# 4046.net
KiCad netlist of a schematic drawn in EasyEDA Pro
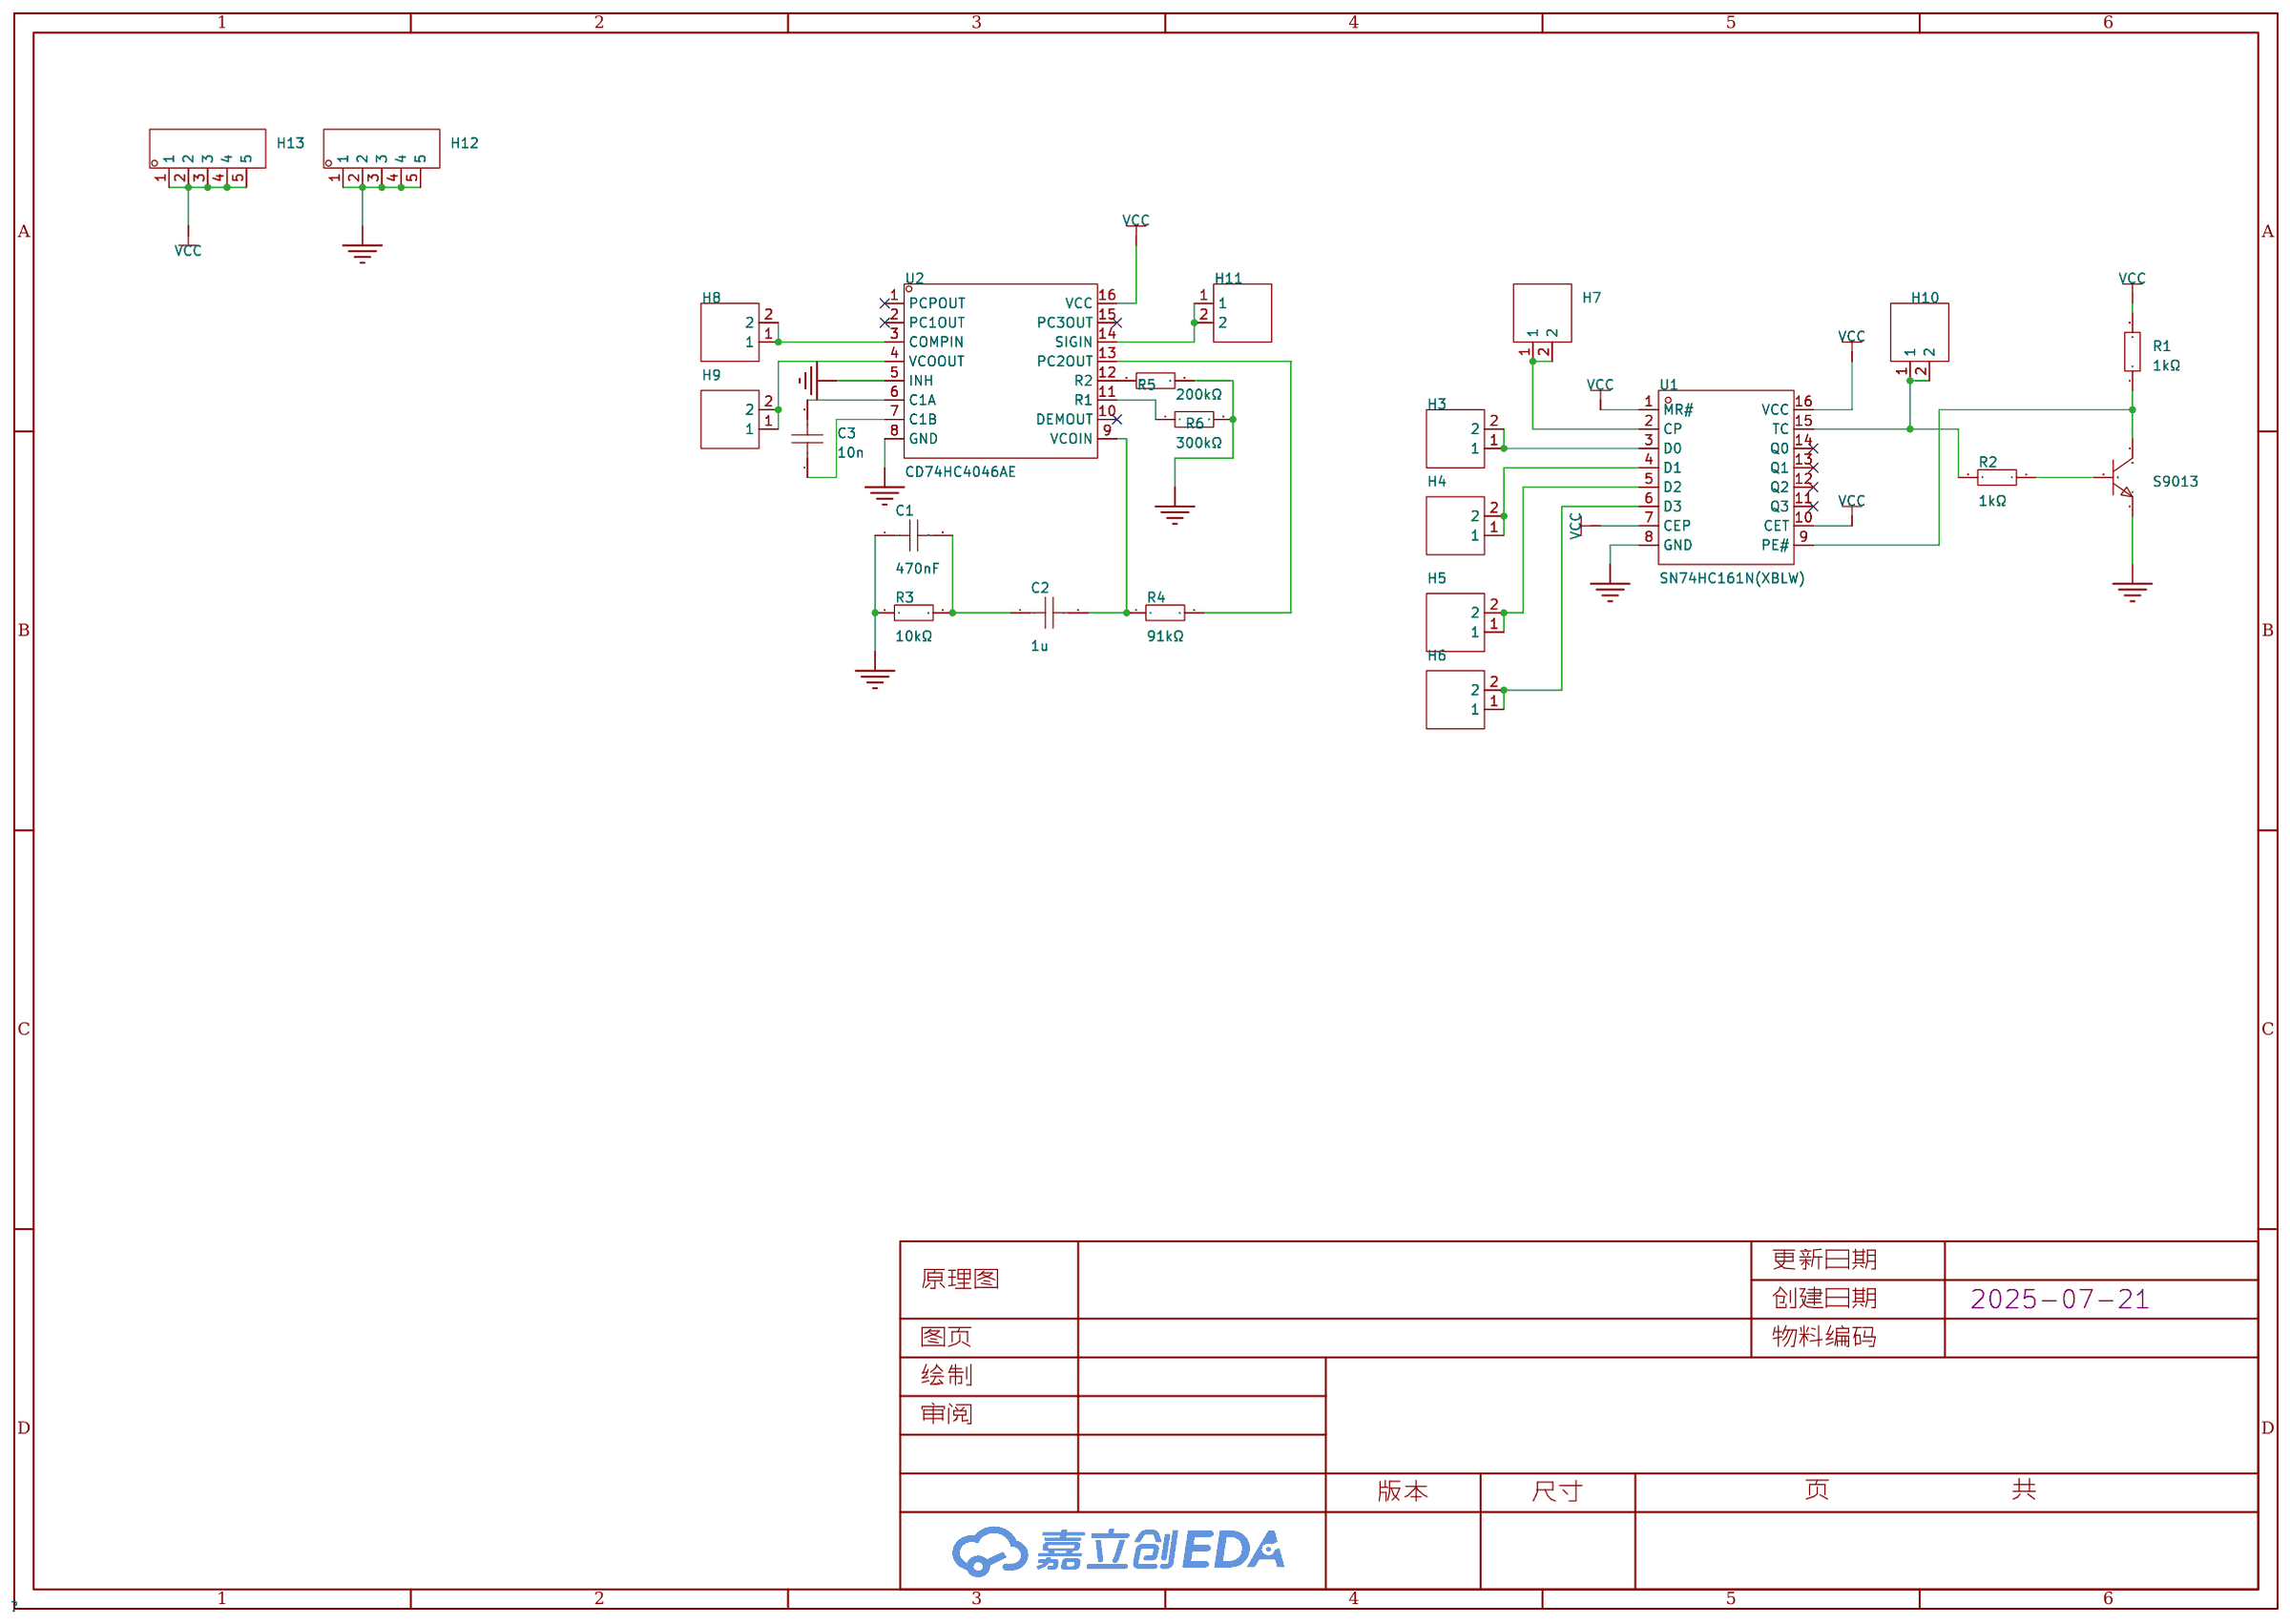
[diagram p0: schematic sheet]

(export (version "E")
  (design (tool "Eeschema 10.0.6"))
  (components
    (comp (ref "C1")
      (value "470nF")
      (footprint "easyedapro:CAP-TH_L8.5-W5.0-P5.00-D1.2")
      (description "容值:100nF;精度:±10%;额定电压:50V;温度系数:X7R;")
      (fields (field (name "Manufacturer Part") "CT4-0805B104K500F3") (field (name "Manufacturer") "FH(风华)"))
      (libsource (lib "easyedapro") (part "CT4-0805B104K500F3"))
    )
    (comp (ref "C2")
      (value "1u")
      (footprint "easyedapro:CAP-TH_L8.5-W5.0-P5.00-D1.2")
      (description "容值:100nF;精度:±10%;额定电压:50V;温度系数:X7R;")
      (fields (field (name "Manufacturer Part") "CT4-0805B104K500F3") (field (name "Manufacturer") "FH(风华)"))
      (libsource (lib "easyedapro") (part "CT4-0805B104K500F3"))
    )
    (comp (ref "C3")
      (value "10n")
      (footprint "easyedapro:CAP-TH_L8.5-W5.0-P5.00-D1.2")
      (description "容值:100nF;精度:±10%;额定电压:50V;温度系数:X7R;")
      (fields (field (name "Manufacturer Part") "CT4-0805B104K500F3") (field (name "Manufacturer") "FH(风华)"))
      (libsource (lib "easyedapro") (part "CT4-0805B104K500F3"))
    )
    (comp (ref "H3")
      (value "~")
      (footprint "easyedapro:HDR-TH_2P-P2.54-V-M-1")
      (libsource (lib "easyedapro") (part "210S-1*2P L=11.6MMGold-plated black"))
    )
    (comp (ref "H4")
      (value "~")
      (footprint "easyedapro:HDR-TH_2P-P2.54-V-M-1")
      (libsource (lib "easyedapro") (part "210S-1*2P L=11.6MMGold-plated black"))
    )
    (comp (ref "H5")
      (value "~")
      (footprint "easyedapro:HDR-TH_2P-P2.54-V-M-1")
      (libsource (lib "easyedapro") (part "210S-1*2P L=11.6MMGold-plated black"))
    )
    (comp (ref "H6")
      (value "~")
      (footprint "easyedapro:HDR-TH_2P-P2.54-V-M-1")
      (libsource (lib "easyedapro") (part "210S-1*2P L=11.6MMGold-plated black"))
    )
    (comp (ref "H7")
      (value "~")
      (footprint "easyedapro:HDR-TH_2P-P2.54-V-M-1")
      (libsource (lib "easyedapro") (part "210S-1*2P L=11.6MMGold-plated black"))
    )
    (comp (ref "H8")
      (value "~")
      (footprint "easyedapro:HDR-TH_2P-P2.54-V-M-1")
      (libsource (lib "easyedapro") (part "210S-1*2P L=11.6MMGold-plated black"))
    )
    (comp (ref "H9")
      (value "~")
      (footprint "easyedapro:HDR-TH_2P-P2.54-V-M-1")
      (libsource (lib "easyedapro") (part "210S-1*2P L=11.6MMGold-plated black"))
    )
    (comp (ref "H10")
      (value "~")
      (footprint "easyedapro:HDR-TH_2P-P2.54-V-M-1")
      (libsource (lib "easyedapro") (part "210S-1*2P L=11.6MMGold-plated black"))
    )
    (comp (ref "H11")
      (value "~")
      (footprint "easyedapro:HDR-TH_2P-P2.54-V-M-1")
      (libsource (lib "easyedapro") (part "210S-1*2P L=11.6MMGold-plated black"))
    )
    (comp (ref "H12")
      (value "~")
      (footprint "easyedapro:HDR-TH_5P-P2.54-V-M")
      (libsource (lib "easyedapro") (part "MTP125-1105S1"))
    )
    (comp (ref "H13")
      (value "~")
      (footprint "easyedapro:HDR-TH_5P-P2.54-V-M")
      (libsource (lib "easyedapro") (part "MTP125-1105S1"))
    )
    (comp (ref "Q1")
      (value "S9013")
      (footprint "easyedapro:TO-92-3_L4.5-W3.5-P1.27-L")
      (description "晶体管类型:NPN;集电极电流(Ic):500mA;直流电流增益(hFE):300;")
      (fields (field (name "Manufacturer") "HXY MOSFET(华轩阳电子)"))
      (libsource (lib "easyedapro") (part "S9013_C20616377"))
    )
    (comp (ref "R1")
      (value "1kΩ")
      (footprint "easyedapro:Res_1/8W")
      (libsource (lib "easyedapro") (part "电阻"))
    )
    (comp (ref "R2")
      (value "1kΩ")
      (footprint "easyedapro:Res_1/8W")
      (libsource (lib "easyedapro") (part "电阻"))
    )
    (comp (ref "R3")
      (value "10kΩ")
      (footprint "easyedapro:Res_1/8W")
      (libsource (lib "easyedapro") (part "电阻"))
    )
    (comp (ref "R4")
      (value "91kΩ")
      (footprint "easyedapro:Res_1/8W")
      (libsource (lib "easyedapro") (part "电阻"))
    )
    (comp (ref "R5")
      (value "200kΩ")
      (footprint "easyedapro:Res_1/8W")
      (libsource (lib "easyedapro") (part "电阻"))
    )
    (comp (ref "R6")
      (value "300kΩ")
      (footprint "easyedapro:Res_1/8W")
      (libsource (lib "easyedapro") (part "电阻"))
    )
    (comp (ref "U1")
      (value "SN74HC161N(XBLW)")
      (footprint "easyedapro:PDIP-16_L19.3-W6.4-P2.54-LS7.9-BL")
      (description "工作电压:2V~6V;触发沿:上升沿;计数速率:48MHz;")
      (fields (field (name "Manufacturer") "XBLW(芯伯乐)"))
      (libsource (lib "easyedapro") (part "SN74HC161N(XBLW)"))
    )
    (comp (ref "U2")
      (value "CD74HC4046AE")
      (footprint "easyedapro:PDIP-16_L22.1-W6.3-P2.54-LS7.6-BL")
      (description "最大输出频率:38MHz;输出通道数:3;")
      (fields (field (name "Manufacturer") "TI(德州仪器)"))
      (libsource (lib "easyedapro") (part "CD74HC4046AE"))
    )
  )
  (nets
    (net (code "1") (name "GND") (class "Default")
      (node (ref "C1") (pin "1") (pinfunction "1_1") (pintype "unspecified"))
      (node (ref "H12") (pin "1") (pinfunction "1_1") (pintype "unspecified"))
      (node (ref "H12") (pin "2") (pinfunction "2_2") (pintype "unspecified"))
      (node (ref "H12") (pin "3") (pinfunction "3_3") (pintype "unspecified"))
      (node (ref "H12") (pin "4") (pinfunction "4_4") (pintype "unspecified"))
      (node (ref "H12") (pin "5") (pinfunction "5_5") (pintype "unspecified"))
      (node (ref "Q1") (pin "1") (pinfunction "E_1") (pintype "unspecified"))
      (node (ref "R3") (pin "1") (pinfunction "1_1") (pintype "input"))
      (node (ref "R5") (pin "2") (pinfunction "2_2") (pintype "input"))
      (node (ref "R6") (pin "2") (pinfunction "2_2") (pintype "input"))
      (node (ref "U1") (pin "8") (pinfunction "GND_8") (pintype "unspecified"))
      (node (ref "U2") (pin "5") (pinfunction "INH_5") (pintype "unspecified"))
      (node (ref "U2") (pin "8") (pinfunction "GND_8") (pintype "unspecified"))
    )
    (net (code "2") (name "Net-(C1-Pad2)") (class "Default")
      (node (ref "C1") (pin "2") (pinfunction "2_2") (pintype "unspecified"))
      (node (ref "C2") (pin "1") (pinfunction "1_1") (pintype "unspecified"))
      (node (ref "R3") (pin "2") (pinfunction "2_2") (pintype "input"))
    )
    (net (code "3") (name "Net-(Q1-B)") (class "Default")
      (node (ref "Q1") (pin "2") (pinfunction "B_2") (pintype "unspecified"))
      (node (ref "R2") (pin "1") (pinfunction "1_1") (pintype "input"))
    )
    (net (code "4") (name "Net-(Q1-C)") (class "Default")
      (node (ref "Q1") (pin "3") (pinfunction "C_3") (pintype "unspecified"))
      (node (ref "R1") (pin "1") (pinfunction "1_1") (pintype "input"))
      (node (ref "U1") (pin "9") (pinfunction "PE#_9") (pintype "unspecified"))
    )
    (net (code "5") (name "Net-(U1-CP)") (class "Default")
      (node (ref "H7") (pin "1") (pinfunction "1_1") (pintype "unspecified"))
      (node (ref "H7") (pin "2") (pinfunction "2_2") (pintype "unspecified"))
      (node (ref "U1") (pin "2") (pinfunction "CP_2") (pintype "unspecified"))
    )
    (net (code "6") (name "Net-(U1-D0)") (class "Default")
      (node (ref "H3") (pin "1") (pinfunction "1_1") (pintype "unspecified"))
      (node (ref "H3") (pin "2") (pinfunction "2_2") (pintype "unspecified"))
      (node (ref "U1") (pin "3") (pinfunction "D0_3") (pintype "unspecified"))
    )
    (net (code "7") (name "Net-(U1-D1)") (class "Default")
      (node (ref "H4") (pin "1") (pinfunction "1_1") (pintype "unspecified"))
      (node (ref "H4") (pin "2") (pinfunction "2_2") (pintype "unspecified"))
      (node (ref "U1") (pin "4") (pinfunction "D1_4") (pintype "unspecified"))
    )
    (net (code "8") (name "Net-(U1-D2)") (class "Default")
      (node (ref "H5") (pin "1") (pinfunction "1_1") (pintype "unspecified"))
      (node (ref "H5") (pin "2") (pinfunction "2_2") (pintype "unspecified"))
      (node (ref "U1") (pin "5") (pinfunction "D2_5") (pintype "unspecified"))
    )
    (net (code "9") (name "Net-(U1-D3)") (class "Default")
      (node (ref "H6") (pin "1") (pinfunction "1_1") (pintype "unspecified"))
      (node (ref "H6") (pin "2") (pinfunction "2_2") (pintype "unspecified"))
      (node (ref "U1") (pin "6") (pinfunction "D3_6") (pintype "unspecified"))
    )
    (net (code "10") (name "Net-(U1-TC)") (class "Default")
      (node (ref "H10") (pin "1") (pinfunction "1_1") (pintype "unspecified"))
      (node (ref "H10") (pin "2") (pinfunction "2_2") (pintype "unspecified"))
      (node (ref "R2") (pin "2") (pinfunction "2_2") (pintype "input"))
      (node (ref "U1") (pin "15") (pinfunction "TC_15") (pintype "unspecified"))
    )
    (net (code "11") (name "Net-(U2-C1A)") (class "Default")
      (node (ref "C3") (pin "2") (pinfunction "2_2") (pintype "unspecified"))
      (node (ref "U2") (pin "6") (pinfunction "C1A_6") (pintype "unspecified"))
    )
    (net (code "12") (name "Net-(U2-C1B)") (class "Default")
      (node (ref "C3") (pin "1") (pinfunction "1_1") (pintype "unspecified"))
      (node (ref "U2") (pin "7") (pinfunction "C1B_7") (pintype "unspecified"))
    )
    (net (code "13") (name "Net-(U2-COMPIN)") (class "Default")
      (node (ref "H8") (pin "1") (pinfunction "1_1") (pintype "unspecified"))
      (node (ref "H8") (pin "2") (pinfunction "2_2") (pintype "unspecified"))
      (node (ref "U2") (pin "3") (pinfunction "COMPIN_3") (pintype "unspecified"))
    )
    (net (code "14") (name "Net-(U2-PC2OUT)") (class "Default")
      (node (ref "R4") (pin "2") (pinfunction "2_2") (pintype "input"))
      (node (ref "U2") (pin "13") (pinfunction "PC2OUT_13") (pintype "unspecified"))
    )
    (net (code "15") (name "Net-(U2-R1)") (class "Default")
      (node (ref "R6") (pin "1") (pinfunction "1_1") (pintype "input"))
      (node (ref "U2") (pin "11") (pinfunction "R1_11") (pintype "unspecified"))
    )
    (net (code "16") (name "Net-(U2-R2)") (class "Default")
      (node (ref "R5") (pin "1") (pinfunction "1_1") (pintype "input"))
      (node (ref "U2") (pin "12") (pinfunction "R2_12") (pintype "unspecified"))
    )
    (net (code "17") (name "Net-(U2-SIGIN)") (class "Default")
      (node (ref "H11") (pin "1") (pinfunction "1_1") (pintype "unspecified"))
      (node (ref "H11") (pin "2") (pinfunction "2_2") (pintype "unspecified"))
      (node (ref "U2") (pin "14") (pinfunction "SIGIN_14") (pintype "unspecified"))
    )
    (net (code "18") (name "Net-(U2-VCOIN)") (class "Default")
      (node (ref "C2") (pin "2") (pinfunction "2_2") (pintype "unspecified"))
      (node (ref "R4") (pin "1") (pinfunction "1_1") (pintype "input"))
      (node (ref "U2") (pin "9") (pinfunction "VCOIN_9") (pintype "unspecified"))
    )
    (net (code "19") (name "Net-(U2-VCOOUT)") (class "Default")
      (node (ref "H9") (pin "1") (pinfunction "1_1") (pintype "unspecified"))
      (node (ref "H9") (pin "2") (pinfunction "2_2") (pintype "unspecified"))
      (node (ref "U2") (pin "4") (pinfunction "VCOOUT_4") (pintype "unspecified"))
    )
    (net (code "20") (name "VCC") (class "Default")
      (node (ref "H13") (pin "1") (pinfunction "1_1") (pintype "unspecified"))
      (node (ref "H13") (pin "2") (pinfunction "2_2") (pintype "unspecified"))
      (node (ref "H13") (pin "3") (pinfunction "3_3") (pintype "unspecified"))
      (node (ref "H13") (pin "4") (pinfunction "4_4") (pintype "unspecified"))
      (node (ref "H13") (pin "5") (pinfunction "5_5") (pintype "unspecified"))
      (node (ref "R1") (pin "2") (pinfunction "2_2") (pintype "input"))
      (node (ref "U1") (pin "1") (pinfunction "MR#_1") (pintype "unspecified"))
      (node (ref "U1") (pin "10") (pinfunction "CET_10") (pintype "unspecified"))
      (node (ref "U1") (pin "16") (pinfunction "VCC_16") (pintype "unspecified"))
      (node (ref "U1") (pin "7") (pinfunction "CEP_7") (pintype "unspecified"))
      (node (ref "U2") (pin "16") (pinfunction "VCC_16") (pintype "unspecified"))
    )
    (net (code "21") (name "unconnected-(U1-Q0-Pad14)") (class "Default")
      (node (ref "U1") (pin "14") (pinfunction "Q0_14") (pintype "unspecified+no_connect"))
    )
    (net (code "22") (name "unconnected-(U1-Q1-Pad13)") (class "Default")
      (node (ref "U1") (pin "13") (pinfunction "Q1_13") (pintype "unspecified+no_connect"))
    )
    (net (code "23") (name "unconnected-(U1-Q2-Pad12)") (class "Default")
      (node (ref "U1") (pin "12") (pinfunction "Q2_12") (pintype "unspecified+no_connect"))
    )
    (net (code "24") (name "unconnected-(U1-Q3-Pad11)") (class "Default")
      (node (ref "U1") (pin "11") (pinfunction "Q3_11") (pintype "unspecified+no_connect"))
    )
    (net (code "25") (name "unconnected-(U2-DEMOUT-Pad10)") (class "Default")
      (node (ref "U2") (pin "10") (pinfunction "DEMOUT_10") (pintype "unspecified+no_connect"))
    )
    (net (code "26") (name "unconnected-(U2-PC1OUT-Pad2)") (class "Default")
      (node (ref "U2") (pin "2") (pinfunction "PC1OUT_2") (pintype "unspecified+no_connect"))
    )
    (net (code "27") (name "unconnected-(U2-PC3OUT-Pad15)") (class "Default")
      (node (ref "U2") (pin "15") (pinfunction "PC3OUT_15") (pintype "unspecified+no_connect"))
    )
    (net (code "28") (name "unconnected-(U2-PCPOUT-Pad1)") (class "Default")
      (node (ref "U2") (pin "1") (pinfunction "PCPOUT_1") (pintype "unspecified+no_connect"))
    )
  )
)
